# tm8_XP1.net
KiCad netlist of a schematic drawn in EAGLE
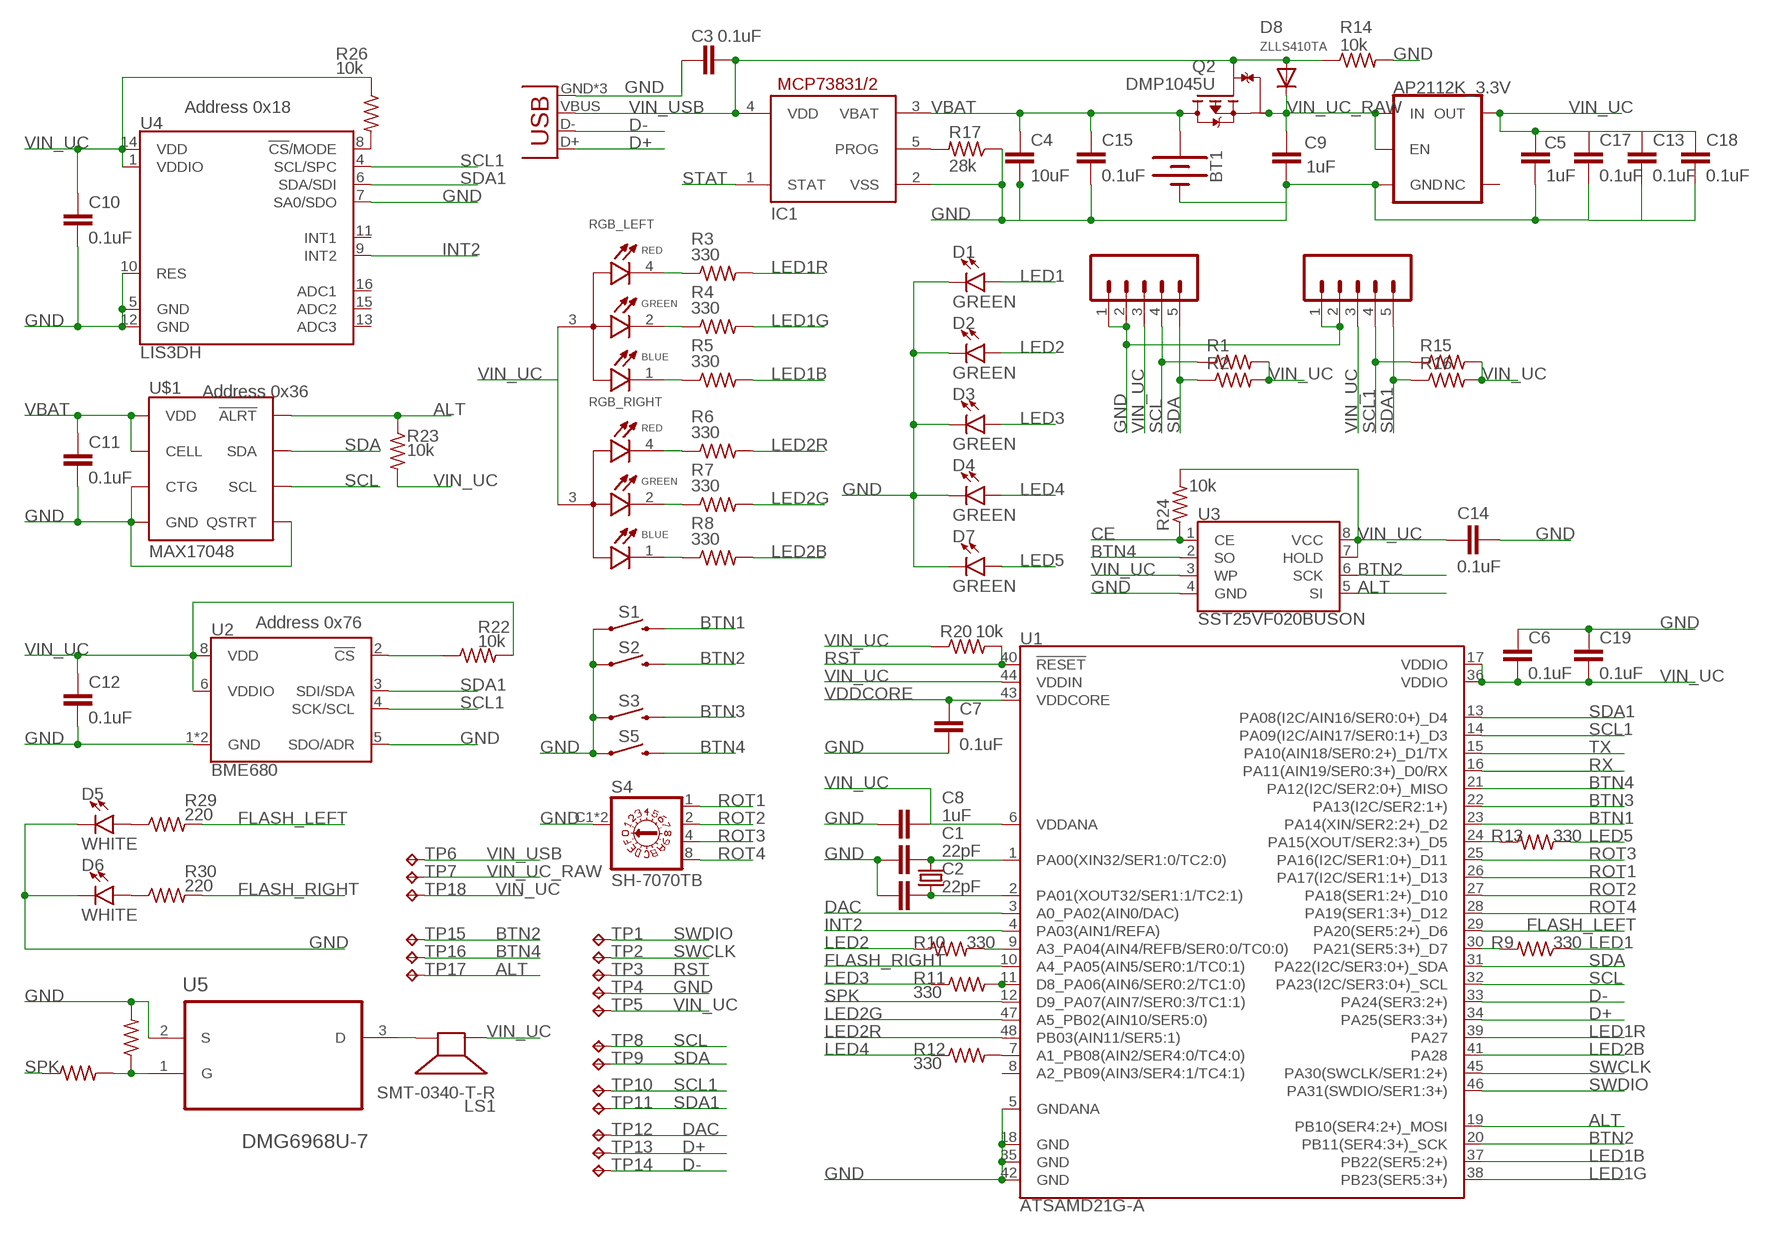
[diagram p0: schematic, sheet 1]

(export (version "E")
  (design (tool "Eeschema 10.0.6"))
  (components
    (comp (ref "AP2112K_3.3V")
      (value "3.3V")
      (footprint "eagle-import:SOT23-5")
      (libsource (lib "eagle-import") (part "V_REG_AP2112K-3.3V"))
    )
    (comp (ref "BT1")
      (value "BATTERY-20MM_SMD_4LEGS_OVERPASTE_INNER")
      (footprint "eagle-import:BATTCON_20MM_4LEGS_OVERPASTE_INNER")
      (libsource (lib "eagle-import") (part "BATTERY-20MM_SMD_4LEGS_OVERPASTE_INNER"))
    )
    (comp (ref "C1")
      (value "22pF")
      (footprint "eagle-import:C0402")
      (libsource (lib "eagle-import") (part "C-EUC0402"))
    )
    (comp (ref "C2")
      (value "22pF")
      (footprint "eagle-import:C0402")
      (libsource (lib "eagle-import") (part "C-EUC0402"))
    )
    (comp (ref "C3")
      (value "0.1uF")
      (footprint "eagle-import:C0402")
      (libsource (lib "eagle-import") (part "C-EUC0402"))
    )
    (comp (ref "C4")
      (value "10uF")
      (footprint "eagle-import:C0402")
      (libsource (lib "eagle-import") (part "C-EUC0402"))
    )
    (comp (ref "C5")
      (value "1uF")
      (footprint "eagle-import:C0402")
      (libsource (lib "eagle-import") (part "C-EUC0402"))
    )
    (comp (ref "C6")
      (value "0.1uF")
      (footprint "eagle-import:C0402")
      (libsource (lib "eagle-import") (part "C-EUC0402"))
    )
    (comp (ref "C7")
      (value "0.1uF")
      (footprint "eagle-import:C0402")
      (libsource (lib "eagle-import") (part "C-EUC0402"))
    )
    (comp (ref "C8")
      (value "1uF")
      (footprint "eagle-import:C0402")
      (libsource (lib "eagle-import") (part "C-EUC0402"))
    )
    (comp (ref "C9")
      (value "1uF")
      (footprint "eagle-import:C0402")
      (libsource (lib "eagle-import") (part "C-EUC0402"))
    )
    (comp (ref "C10")
      (value "0.1uF")
      (footprint "eagle-import:C0402")
      (libsource (lib "eagle-import") (part "C-EUC0402"))
    )
    (comp (ref "C11")
      (value "0.1uF")
      (footprint "eagle-import:C0402")
      (libsource (lib "eagle-import") (part "C-EUC0402"))
    )
    (comp (ref "C12")
      (value "0.1uF")
      (footprint "eagle-import:C0402")
      (libsource (lib "eagle-import") (part "C-EUC0402"))
    )
    (comp (ref "C13")
      (value "0.1uF")
      (footprint "eagle-import:C0402")
      (libsource (lib "eagle-import") (part "C-EUC0402"))
    )
    (comp (ref "C14")
      (value "0.1uF")
      (footprint "eagle-import:C0402")
      (libsource (lib "eagle-import") (part "C-EUC0402"))
    )
    (comp (ref "C15")
      (value "0.1uF")
      (footprint "eagle-import:C0402")
      (libsource (lib "eagle-import") (part "C-EUC0402"))
    )
    (comp (ref "C17")
      (value "0.1uF")
      (footprint "eagle-import:C0402")
      (libsource (lib "eagle-import") (part "C-EUC0402"))
    )
    (comp (ref "C18")
      (value "0.1uF")
      (footprint "eagle-import:C0402")
      (libsource (lib "eagle-import") (part "C-EUC0402"))
    )
    (comp (ref "C19")
      (value "0.1uF")
      (footprint "eagle-import:C0402")
      (libsource (lib "eagle-import") (part "C-EUC0402"))
    )
    (comp (ref "D1")
      (value "GREEN")
      (footprint "eagle-import:LED-1206")
      (libsource (lib "eagle-import") (part "LED-GREEN1206"))
    )
    (comp (ref "D2")
      (value "GREEN")
      (footprint "eagle-import:LED-1206")
      (libsource (lib "eagle-import") (part "LED-GREEN1206"))
    )
    (comp (ref "D3")
      (value "GREEN")
      (footprint "eagle-import:LED-1206")
      (libsource (lib "eagle-import") (part "LED-GREEN1206"))
    )
    (comp (ref "D4")
      (value "GREEN")
      (footprint "eagle-import:LED-1206")
      (libsource (lib "eagle-import") (part "LED-GREEN1206"))
    )
    (comp (ref "D5")
      (value "WHITE")
      (footprint "eagle-import:LED-1206")
      (libsource (lib "eagle-import") (part "LED-WHITE1206"))
    )
    (comp (ref "D6")
      (value "WHITE")
      (footprint "eagle-import:LED-1206")
      (libsource (lib "eagle-import") (part "LED-WHITE1206"))
    )
    (comp (ref "D7")
      (value "GREEN")
      (footprint "eagle-import:LED-1206")
      (libsource (lib "eagle-import") (part "LED-GREEN1206"))
    )
    (comp (ref "D8")
      (value "ZLLS410TA")
      (footprint "eagle-import:SOD-323F")
      (libsource (lib "eagle-import") (part "DIODESOD-323F"))
    )
    (comp (ref "IC1")
      (value "MCP73831/OT")
      (footprint "eagle-import:SOT23-5L")
      (libsource (lib "eagle-import") (part "MCP73831/OT"))
    )
    (comp (ref "JP2")
      (value "USB-MICROB")
      (footprint "eagle-import:USB-MICROB")
      (libsource (lib "eagle-import") (part "USB-MICROB"))
    )
    (comp (ref "LCD1")
      (value "CONN_05VERT_FEMALE_HEADER")
      (footprint "eagle-import:1X05_SMD_VERTICAL_COMBO")
      (libsource (lib "eagle-import") (part "CONN_05VERT_FEMALE_HEADER"))
    )
    (comp (ref "LCD2")
      (value "CONN_05VERT_FEMALE_HEADER")
      (footprint "eagle-import:1X05_SMD_VERTICAL_COMBO")
      (libsource (lib "eagle-import") (part "CONN_05VERT_FEMALE_HEADER"))
    )
    (comp (ref "LS1")
      (value "SMT-0340-T-R")
      (footprint "eagle-import:XDCR_SMT-0340-T-R")
      (fields (field (name "MANUFACTURER") "Pui Audio"))
      (libsource (lib "eagle-import") (part "SMT-0340-T-R"))
    )
    (comp (ref "Q2")
      (value "DMP1045U")
      (footprint "eagle-import:SOT91P240X110-3N")
      (fields (field (name "MF") "Diodes Inc."))
      (libsource (lib "eagle-import") (part "DMP1045U"))
    )
    (comp (ref "R1")
      (value "R-US_R0402")
      (footprint "eagle-import:R0402")
      (libsource (lib "eagle-import") (part "adafruit_25768682_R-US_R0402"))
    )
    (comp (ref "R2")
      (value "R-US_R0402")
      (footprint "eagle-import:R0402")
      (libsource (lib "eagle-import") (part "adafruit_25768682_R-US_R0402"))
    )
    (comp (ref "R3")
      (value "330")
      (footprint "eagle-import:R0402")
      (libsource (lib "eagle-import") (part "rcl_334_R-US_R0402"))
    )
    (comp (ref "R4")
      (value "330")
      (footprint "eagle-import:R0402")
      (libsource (lib "eagle-import") (part "rcl_334_R-US_R0402"))
    )
    (comp (ref "R5")
      (value "330")
      (footprint "eagle-import:R0402")
      (libsource (lib "eagle-import") (part "rcl_334_R-US_R0402"))
    )
    (comp (ref "R6")
      (value "330")
      (footprint "eagle-import:R0402")
      (libsource (lib "eagle-import") (part "rcl_334_R-US_R0402"))
    )
    (comp (ref "R7")
      (value "330")
      (footprint "eagle-import:R0402")
      (libsource (lib "eagle-import") (part "rcl_334_R-US_R0402"))
    )
    (comp (ref "R8")
      (value "330")
      (footprint "eagle-import:R0402")
      (libsource (lib "eagle-import") (part "rcl_334_R-US_R0402"))
    )
    (comp (ref "R9")
      (value "330")
      (footprint "eagle-import:R0402")
      (libsource (lib "eagle-import") (part "rcl_334_R-US_R0402"))
    )
    (comp (ref "R10")
      (value "330")
      (footprint "eagle-import:R0402")
      (libsource (lib "eagle-import") (part "rcl_334_R-US_R0402"))
    )
    (comp (ref "R11")
      (value "330")
      (footprint "eagle-import:R0402")
      (libsource (lib "eagle-import") (part "rcl_334_R-US_R0402"))
    )
    (comp (ref "R12")
      (value "330")
      (footprint "eagle-import:R0402")
      (libsource (lib "eagle-import") (part "rcl_334_R-US_R0402"))
    )
    (comp (ref "R13")
      (value "330")
      (footprint "eagle-import:R0402")
      (libsource (lib "eagle-import") (part "rcl_334_R-US_R0402"))
    )
    (comp (ref "R14")
      (value "10k")
      (footprint "eagle-import:R0402")
      (libsource (lib "eagle-import") (part "R-US_R0402"))
    )
    (comp (ref "R15")
      (value "R-US_R0402")
      (footprint "eagle-import:R0402")
      (libsource (lib "eagle-import") (part "adafruit_25768682_R-US_R0402"))
    )
    (comp (ref "R16")
      (value "R-US_R0402")
      (footprint "eagle-import:R0402")
      (libsource (lib "eagle-import") (part "adafruit_25768682_R-US_R0402"))
    )
    (comp (ref "R17")
      (value "28k")
      (footprint "eagle-import:R0402")
      (libsource (lib "eagle-import") (part "adafruit_25768682_R-US_R0402"))
    )
    (comp (ref "R18")
      (value "220")
      (footprint "eagle-import:R0402")
      (libsource (lib "eagle-import") (part "rcl_334_R-US_R0402"))
    )
    (comp (ref "R19")
      (value "220")
      (footprint "eagle-import:R0402")
      (libsource (lib "eagle-import") (part "rcl_334_R-US_R0402"))
    )
    (comp (ref "R20")
      (value "10k")
      (footprint "eagle-import:R0402")
      (libsource (lib "eagle-import") (part "adafruit_25768682_R-US_R0402"))
    )
    (comp (ref "R22")
      (value "10k")
      (footprint "eagle-import:R0402")
      (libsource (lib "eagle-import") (part "rcl_334_R-US_R0402"))
    )
    (comp (ref "R23")
      (value "10k")
      (footprint "eagle-import:R0402")
      (libsource (lib "eagle-import") (part "rcl_334_R-US_R0402"))
    )
    (comp (ref "R24")
      (value "10k")
      (footprint "eagle-import:R0402")
      (libsource (lib "eagle-import") (part "rcl_334_R-US_R0402"))
    )
    (comp (ref "R26")
      (value "10k")
      (footprint "eagle-import:R0402")
      (libsource (lib "eagle-import") (part "rcl_334_R-US_R0402"))
    )
    (comp (ref "R29")
      (value "220")
      (footprint "eagle-import:R0402")
      (libsource (lib "eagle-import") (part "rcl_334_R-US_R0402"))
    )
    (comp (ref "R30")
      (value "220")
      (footprint "eagle-import:R0402")
      (libsource (lib "eagle-import") (part "rcl_334_R-US_R0402"))
    )
    (comp (ref "RGB_LEFT")
      (value "EAST1616RGBA3")
      (footprint "eagle-import:LED_EAST1616RGBA3")
      (fields (field (name "MF") "Everlight Electronics"))
      (libsource (lib "eagle-import") (part "EAST1616RGBA3"))
    )
    (comp (ref "RGB_RIGHT")
      (value "EAST1616RGBA3")
      (footprint "eagle-import:LED_EAST1616RGBA3")
      (fields (field (name "MF") "Everlight Electronics"))
      (libsource (lib "eagle-import") (part "EAST1616RGBA3"))
    )
    (comp (ref "S1")
      (value "MOMENTARY-SWITCH-SPST-SMD-6.0X3.5MM")
      (footprint "eagle-import:TACTILE_SWITCH_SMD_6.0X3.5MM")
      (libsource (lib "eagle-import") (part "MOMENTARY-SWITCH-SPST-SMD-6.0X3.5MM"))
    )
    (comp (ref "S2")
      (value "MOMENTARY-SWITCH-SPST-SMD-6.0X3.5MM")
      (footprint "eagle-import:TACTILE_SWITCH_SMD_6.0X3.5MM")
      (libsource (lib "eagle-import") (part "MOMENTARY-SWITCH-SPST-SMD-6.0X3.5MM"))
    )
    (comp (ref "S3")
      (value "MOMENTARY-SWITCH-SPST-SMD-6.0X3.5MM")
      (footprint "eagle-import:TACTILE_SWITCH_SMD_6.0X3.5MM")
      (libsource (lib "eagle-import") (part "MOMENTARY-SWITCH-SPST-SMD-6.0X3.5MM"))
    )
    (comp (ref "S4")
      (value "SH-7070TB")
      (footprint "eagle-import:SH-7070B")
      (fields (field (name "MF") "Nidec Copal"))
      (libsource (lib "eagle-import") (part "SH-7070TB"))
    )
    (comp (ref "S5")
      (value "MOMENTARY-SWITCH-SPST-SMD-6.0X3.5MM")
      (footprint "eagle-import:TACTILE_SWITCH_SMD_6.0X3.5MM")
      (libsource (lib "eagle-import") (part "MOMENTARY-SWITCH-SPST-SMD-6.0X3.5MM"))
    )
    (comp (ref "TP1")
      (value "TPTP14R")
      (footprint "eagle-import:TP14R")
      (libsource (lib "eagle-import") (part "TPTP14R"))
    )
    (comp (ref "TP2")
      (value "TPTP14R")
      (footprint "eagle-import:TP14R")
      (libsource (lib "eagle-import") (part "TPTP14R"))
    )
    (comp (ref "TP3")
      (value "TPTP14R")
      (footprint "eagle-import:TP14R")
      (libsource (lib "eagle-import") (part "TPTP14R"))
    )
    (comp (ref "TP4")
      (value "TPTP14R")
      (footprint "eagle-import:TP14R")
      (libsource (lib "eagle-import") (part "TPTP14R"))
    )
    (comp (ref "TP5")
      (value "TPTP14R")
      (footprint "eagle-import:TP14R")
      (libsource (lib "eagle-import") (part "TPTP14R"))
    )
    (comp (ref "TP6")
      (value "TPTP14R")
      (footprint "eagle-import:TP14R")
      (libsource (lib "eagle-import") (part "TPTP14R"))
    )
    (comp (ref "TP7")
      (value "TPTP14R")
      (footprint "eagle-import:TP14R")
      (libsource (lib "eagle-import") (part "TPTP14R"))
    )
    (comp (ref "TP8")
      (value "TPTP14R")
      (footprint "eagle-import:TP14R")
      (libsource (lib "eagle-import") (part "TPTP14R"))
    )
    (comp (ref "TP9")
      (value "TPTP14R")
      (footprint "eagle-import:TP14R")
      (libsource (lib "eagle-import") (part "TPTP14R"))
    )
    (comp (ref "TP10")
      (value "TPTP14R")
      (footprint "eagle-import:TP14R")
      (libsource (lib "eagle-import") (part "TPTP14R"))
    )
    (comp (ref "TP11")
      (value "TPTP14R")
      (footprint "eagle-import:TP14R")
      (libsource (lib "eagle-import") (part "TPTP14R"))
    )
    (comp (ref "TP12")
      (value "TPTP14R")
      (footprint "eagle-import:TP14R")
      (libsource (lib "eagle-import") (part "TPTP14R"))
    )
    (comp (ref "TP13")
      (value "TPTP14R")
      (footprint "eagle-import:TP14R")
      (libsource (lib "eagle-import") (part "TPTP14R"))
    )
    (comp (ref "TP14")
      (value "TPTP14R")
      (footprint "eagle-import:TP14R")
      (libsource (lib "eagle-import") (part "TPTP14R"))
    )
    (comp (ref "TP15")
      (value "TPTP14R")
      (footprint "eagle-import:TP14R")
      (libsource (lib "eagle-import") (part "TPTP14R"))
    )
    (comp (ref "TP16")
      (value "TPTP14R")
      (footprint "eagle-import:TP14R")
      (libsource (lib "eagle-import") (part "TPTP14R"))
    )
    (comp (ref "TP17")
      (value "TPTP14R")
      (footprint "eagle-import:TP14R")
      (libsource (lib "eagle-import") (part "TPTP14R"))
    )
    (comp (ref "TP18")
      (value "TPTP14R")
      (footprint "eagle-import:TP14R")
      (libsource (lib "eagle-import") (part "TPTP14R"))
    )
    (comp (ref "U$1")
      (value "MAX17048")
      (footprint "eagle-import:DFN-8")
      (libsource (lib "eagle-import") (part "MAX17048DFN8"))
    )
    (comp (ref "U1")
      (value "ATSAMD21G-A")
      (footprint "eagle-import:TQFP-48")
      (libsource (lib "eagle-import") (part "ATSAMD21G-A"))
    )
    (comp (ref "U2")
      (value "BME680")
      (footprint "eagle-import:LGA3.0X3.0")
      (libsource (lib "eagle-import") (part "BME680-LGA"))
    )
    (comp (ref "U3")
      (value "SST25VF020BUSON")
      (footprint "eagle-import:USON_3X2MM")
      (fields
        (field (name "DIGIKEY_PART") "SST25VF020B-80-4I-Q3AE-TCT-ND")
        (field (name "MANU_PART") "SST25VF020B-80-4I-Q3AE-T")
      )
      (libsource (lib "eagle-import") (part "SST25VF020BUSON"))
    )
    (comp (ref "U4")
      (value "LIS3DH")
      (footprint "eagle-import:LGA-16-3X3")
      (libsource (lib "eagle-import") (part "LIS3DH"))
    )
    (comp (ref "U5")
      (value "DMG6968U-7")
      (footprint "eagle-import:SOT95P240X110-3N")
      (fields (field (name "MF") "Diodes Inc."))
      (libsource (lib "eagle-import") (part "DMG6968U-7"))
    )
    (comp (ref "Y1")
      (value "32.768kHz")
      (footprint "eagle-import:CRYSTAL-SMD-3.2X1.5MM")
      (libsource (lib "eagle-import") (part "CRYSTAL-32.768KHZSMD-3.2X1.5"))
    )
  )
  (nets
    (net (code "1") (name "/ALT") (class "Default")
      (node (ref "R23") (pin "1") (pinfunction "1_1") (pintype "passive"))
      (node (ref "TP17") (pin "TP") (pinfunction "TP_TP") (pintype "input"))
      (node (ref "U$1") (pin "P$5") (pinfunction "~{ALRT}_P$5") (pintype "bidirectional"))
      (node (ref "U1") (pin "19") (pinfunction "PB10(SER4:2+)_MOSI_19") (pintype "bidirectional"))
      (node (ref "U3") (pin "5") (pinfunction "SI_5") (pintype "bidirectional"))
    )
    (net (code "2") (name "/BTN1") (class "Default")
      (node (ref "S1") (pin "2") (pinfunction "2_2") (pintype "passive"))
      (node (ref "U1") (pin "23") (pinfunction "PA14(XIN/SER2:2+)_D2_23") (pintype "bidirectional"))
    )
    (net (code "3") (name "/BTN2") (class "Default")
      (node (ref "S2") (pin "2") (pinfunction "2_2") (pintype "passive"))
      (node (ref "TP15") (pin "TP") (pinfunction "TP_TP") (pintype "input"))
      (node (ref "U1") (pin "20") (pinfunction "PB11(SER4:3+)_SCK_20") (pintype "bidirectional"))
      (node (ref "U3") (pin "6") (pinfunction "SCK_6") (pintype "bidirectional"))
    )
    (net (code "4") (name "/BTN3") (class "Default")
      (node (ref "S3") (pin "2") (pinfunction "2_2") (pintype "passive"))
      (node (ref "U1") (pin "22") (pinfunction "PA13(I2C/SER2:1+)_22") (pintype "bidirectional"))
    )
    (net (code "5") (name "/BTN4") (class "Default")
      (node (ref "S5") (pin "2") (pinfunction "2_2") (pintype "passive"))
      (node (ref "TP16") (pin "TP") (pinfunction "TP_TP") (pintype "input"))
      (node (ref "U1") (pin "21") (pinfunction "PA12(I2C/SER2:0+)_MISO_21") (pintype "bidirectional"))
      (node (ref "U3") (pin "2") (pinfunction "SO_2") (pintype "bidirectional"))
    )
    (net (code "6") (name "/CE") (class "Default")
      (node (ref "R24") (pin "1") (pinfunction "1_1") (pintype "passive"))
      (node (ref "U3") (pin "1") (pinfunction "CE_1") (pintype "bidirectional"))
    )
    (net (code "7") (name "/D+") (class "Default")
      (node (ref "JP2") (pin "D+") (pinfunction "D+_D+") (pintype "bidirectional"))
      (node (ref "TP13") (pin "TP") (pinfunction "TP_TP") (pintype "input"))
      (node (ref "U1") (pin "34") (pinfunction "PA25(SER3:3+)_34") (pintype "bidirectional"))
    )
    (net (code "8") (name "/D-") (class "Default")
      (node (ref "JP2") (pin "D-") (pinfunction "D-_D-") (pintype "bidirectional"))
      (node (ref "TP14") (pin "TP") (pinfunction "TP_TP") (pintype "input"))
      (node (ref "U1") (pin "33") (pinfunction "PA24(SER3:2+)_33") (pintype "bidirectional"))
    )
    (net (code "9") (name "/DAC") (class "Default")
      (node (ref "TP12") (pin "TP") (pinfunction "TP_TP") (pintype "input"))
      (node (ref "U1") (pin "3") (pinfunction "A0_PA02(AIN0/DAC)_3") (pintype "bidirectional"))
    )
    (net (code "10") (name "/FLASH_LEFT") (class "Default")
      (node (ref "R29") (pin "2") (pinfunction "2_2") (pintype "passive"))
      (node (ref "U1") (pin "29") (pinfunction "PA20(SER5:2+)_D6_29") (pintype "bidirectional"))
    )
    (net (code "11") (name "/FLASH_RIGHT") (class "Default")
      (node (ref "R30") (pin "2") (pinfunction "2_2") (pintype "passive"))
      (node (ref "U1") (pin "10") (pinfunction "A4_PA05(AIN5/SER0:1/TC0:1)_10") (pintype "bidirectional"))
    )
    (net (code "12") (name "/GND") (class "Default")
      (node (ref "AP2112K_3.3V") (pin "2") (pinfunction "GND_2") (pintype "input"))
      (node (ref "BT1") (pin "2") (pinfunction "-_2") (pintype "power_in"))
      (node (ref "C1") (pin "1") (pinfunction "1_1") (pintype "passive"))
      (node (ref "C10") (pin "2") (pinfunction "2_2") (pintype "passive"))
      (node (ref "C11") (pin "2") (pinfunction "2_2") (pintype "passive"))
      (node (ref "C12") (pin "2") (pinfunction "2_2") (pintype "passive"))
      (node (ref "C13") (pin "2") (pinfunction "2_2") (pintype "passive"))
      (node (ref "C14") (pin "2") (pinfunction "2_2") (pintype "passive"))
      (node (ref "C15") (pin "2") (pinfunction "2_2") (pintype "passive"))
      (node (ref "C17") (pin "2") (pinfunction "2_2") (pintype "passive"))
      (node (ref "C18") (pin "2") (pinfunction "2_2") (pintype "passive"))
      (node (ref "C19") (pin "1") (pinfunction "1_1") (pintype "passive"))
      (node (ref "C2") (pin "1") (pinfunction "1_1") (pintype "passive"))
      (node (ref "C3") (pin "1") (pinfunction "1_1") (pintype "passive"))
      (node (ref "C4") (pin "2") (pinfunction "2_2") (pintype "passive"))
      (node (ref "C5") (pin "2") (pinfunction "2_2") (pintype "passive"))
      (node (ref "C6") (pin "1") (pinfunction "1_1") (pintype "passive"))
      (node (ref "C7") (pin "2") (pinfunction "2_2") (pintype "passive"))
      (node (ref "C8") (pin "1") (pinfunction "1_1") (pintype "passive"))
      (node (ref "C9") (pin "2") (pinfunction "2_2") (pintype "passive"))
      (node (ref "D1") (pin "C") (pinfunction "C_C") (pintype "passive"))
      (node (ref "D2") (pin "C") (pinfunction "C_C") (pintype "passive"))
      (node (ref "D3") (pin "C") (pinfunction "C_C") (pintype "passive"))
      (node (ref "D4") (pin "C") (pinfunction "C_C") (pintype "passive"))
      (node (ref "D5") (pin "C") (pinfunction "C_C") (pintype "passive"))
      (node (ref "D6") (pin "C") (pinfunction "C_C") (pintype "passive"))
      (node (ref "D7") (pin "C") (pinfunction "C_C") (pintype "passive"))
      (node (ref "IC1") (pin "2") (pinfunction "VSS_2") (pintype "power_in"))
      (node (ref "JP2") (pin "GND") (pinfunction "GND_GND") (pintype "bidirectional"))
      (node (ref "JP2") (pin "MT1") (pinfunction "GND_MT1") (pintype "bidirectional"))
      (node (ref "JP2") (pin "MT2") (pinfunction "GND_MT2") (pintype "bidirectional"))
      (node (ref "LCD1") (pin "1") (pinfunction "1_1") (pintype "passive"))
      (node (ref "LCD1") (pin "2") (pinfunction "2_2") (pintype "passive"))
      (node (ref "LCD2") (pin "1") (pinfunction "1_1") (pintype "passive"))
      (node (ref "LCD2") (pin "2") (pinfunction "2_2") (pintype "passive"))
      (node (ref "R14") (pin "2") (pinfunction "2_2") (pintype "passive"))
      (node (ref "R17") (pin "1") (pinfunction "1_1") (pintype "passive"))
      (node (ref "R19") (pin "2") (pinfunction "2_2") (pintype "passive"))
      (node (ref "S1") (pin "1") (pinfunction "1_1") (pintype "passive"))
      (node (ref "S2") (pin "1") (pinfunction "1_1") (pintype "passive"))
      (node (ref "S3") (pin "1") (pinfunction "1_1") (pintype "passive"))
      (node (ref "S4") (pin "C1") (pinfunction "C_C1") (pintype "passive"))
      (node (ref "S4") (pin "C2") (pinfunction "C_C2") (pintype "passive"))
      (node (ref "S5") (pin "1") (pinfunction "1_1") (pintype "passive"))
      (node (ref "TP4") (pin "TP") (pinfunction "TP_TP") (pintype "input"))
      (node (ref "U$1") (pin "P$1") (pinfunction "CTG_P$1") (pintype "input"))
      (node (ref "U$1") (pin "P$4") (pinfunction "GND_P$4") (pintype "bidirectional"))
      (node (ref "U$1") (pin "P$6") (pinfunction "QSTRT_P$6") (pintype "bidirectional"))
      (node (ref "U$1") (pin "P$9") (pinfunction "GND_P$9") (pintype "bidirectional"))
      (node (ref "U1") (pin "18") (pinfunction "GND_18") (pintype "bidirectional"))
      (node (ref "U1") (pin "35") (pinfunction "GND_35") (pintype "bidirectional"))
      (node (ref "U1") (pin "42") (pinfunction "GND_42") (pintype "bidirectional"))
      (node (ref "U1") (pin "5") (pinfunction "GNDANA_5") (pintype "bidirectional"))
      (node (ref "U2") (pin "1") (pinfunction "GND_1") (pintype "bidirectional"))
      (node (ref "U2") (pin "5") (pinfunction "SDO/ADR_5") (pintype "bidirectional"))
      (node (ref "U2") (pin "7") (pinfunction "GND_7") (pintype "bidirectional"))
      (node (ref "U3") (pin "4") (pinfunction "GND_4") (pintype "power_in"))
      (node (ref "U4") (pin "10") (pinfunction "RES_10") (pintype "bidirectional"))
      (node (ref "U4") (pin "12") (pinfunction "GND_12") (pintype "bidirectional"))
      (node (ref "U4") (pin "5") (pinfunction "GND_5") (pintype "bidirectional"))
      (node (ref "U4") (pin "7") (pinfunction "SA0/SDO_7") (pintype "bidirectional"))
      (node (ref "U5") (pin "2") (pinfunction "S_2") (pintype "passive"))
    )
    (net (code "13") (name "/INT2") (class "Default")
      (node (ref "U1") (pin "4") (pinfunction "PA03(AIN1/REFA)_4") (pintype "bidirectional"))
      (node (ref "U4") (pin "9") (pinfunction "INT2_9") (pintype "bidirectional"))
    )
    (net (code "14") (name "/LED1") (class "Default")
      (node (ref "D1") (pin "A") (pinfunction "A_A") (pintype "passive"))
      (node (ref "R9") (pin "1") (pinfunction "1_1") (pintype "passive"))
    )
    (net (code "15") (name "/LED1B") (class "Default")
      (node (ref "R5") (pin "2") (pinfunction "2_2") (pintype "passive"))
      (node (ref "U1") (pin "37") (pinfunction "PB22(SER5:2+)_37") (pintype "bidirectional"))
    )
    (net (code "16") (name "/LED1G") (class "Default")
      (node (ref "R4") (pin "2") (pinfunction "2_2") (pintype "passive"))
      (node (ref "U1") (pin "38") (pinfunction "PB23(SER5:3+)_38") (pintype "bidirectional"))
    )
    (net (code "17") (name "/LED1R") (class "Default")
      (node (ref "R3") (pin "2") (pinfunction "2_2") (pintype "passive"))
      (node (ref "U1") (pin "39") (pinfunction "PA27_39") (pintype "bidirectional"))
    )
    (net (code "18") (name "/LED2") (class "Default")
      (node (ref "D2") (pin "A") (pinfunction "A_A") (pintype "passive"))
      (node (ref "R10") (pin "1") (pinfunction "1_1") (pintype "passive"))
    )
    (net (code "19") (name "/LED2B") (class "Default")
      (node (ref "R8") (pin "2") (pinfunction "2_2") (pintype "passive"))
      (node (ref "U1") (pin "41") (pinfunction "PA28_41") (pintype "bidirectional"))
    )
    (net (code "20") (name "/LED2G") (class "Default")
      (node (ref "R7") (pin "2") (pinfunction "2_2") (pintype "passive"))
      (node (ref "U1") (pin "47") (pinfunction "A5_PB02(AIN10/SER5:0)_47") (pintype "bidirectional"))
    )
    (net (code "21") (name "/LED2R") (class "Default")
      (node (ref "R6") (pin "2") (pinfunction "2_2") (pintype "passive"))
      (node (ref "U1") (pin "48") (pinfunction "PB03(AIN11/SER5:1)_48") (pintype "bidirectional"))
    )
    (net (code "22") (name "/LED3") (class "Default")
      (node (ref "D3") (pin "A") (pinfunction "A_A") (pintype "passive"))
      (node (ref "R11") (pin "1") (pinfunction "1_1") (pintype "passive"))
    )
    (net (code "23") (name "/LED4") (class "Default")
      (node (ref "D4") (pin "A") (pinfunction "A_A") (pintype "passive"))
      (node (ref "R12") (pin "1") (pinfunction "1_1") (pintype "passive"))
    )
    (net (code "24") (name "/LED5") (class "Default")
      (node (ref "D7") (pin "A") (pinfunction "A_A") (pintype "passive"))
      (node (ref "R13") (pin "2") (pinfunction "2_2") (pintype "passive"))
    )
    (net (code "25") (name "/ROT1") (class "Default")
      (node (ref "S4") (pin "1") (pinfunction "1_1") (pintype "passive"))
      (node (ref "U1") (pin "26") (pinfunction "PA17(I2C/SER1:1+)_D13_26") (pintype "bidirectional"))
    )
    (net (code "26") (name "/ROT2") (class "Default")
      (node (ref "S4") (pin "2") (pinfunction "2_2") (pintype "passive"))
      (node (ref "U1") (pin "27") (pinfunction "PA18(SER1:2+)_D10_27") (pintype "bidirectional"))
    )
    (net (code "27") (name "/ROT3") (class "Default")
      (node (ref "S4") (pin "4") (pinfunction "4_4") (pintype "passive"))
      (node (ref "U1") (pin "25") (pinfunction "PA16(I2C/SER1:0+)_D11_25") (pintype "bidirectional"))
    )
    (net (code "28") (name "/ROT4") (class "Default")
      (node (ref "S4") (pin "8") (pinfunction "8_8") (pintype "passive"))
      (node (ref "U1") (pin "28") (pinfunction "PA19(SER1:3+)_D12_28") (pintype "bidirectional"))
    )
    (net (code "29") (name "/RST") (class "Default")
      (node (ref "R20") (pin "2") (pinfunction "2_2") (pintype "passive"))
      (node (ref "TP3") (pin "TP") (pinfunction "TP_TP") (pintype "input"))
      (node (ref "U1") (pin "40") (pinfunction "~{RESET}_40") (pintype "bidirectional"))
    )
    (net (code "30") (name "/RX") (class "Default")
      (node (ref "U1") (pin "16") (pinfunction "PA11(AIN19/SER0:3+)_D0/RX_16") (pintype "bidirectional"))
    )
    (net (code "31") (name "/SCL") (class "Default")
      (node (ref "LCD1") (pin "4") (pinfunction "4_4") (pintype "passive"))
      (node (ref "R1") (pin "1") (pinfunction "1_1") (pintype "passive"))
      (node (ref "TP8") (pin "TP") (pinfunction "TP_TP") (pintype "input"))
      (node (ref "U$1") (pin "P$7") (pinfunction "SCL_P$7") (pintype "output"))
      (node (ref "U1") (pin "32") (pinfunction "PA23(I2C/SER3:0+)_SCL_32") (pintype "bidirectional"))
    )
    (net (code "32") (name "/SCL1") (class "Default")
      (node (ref "LCD2") (pin "4") (pinfunction "4_4") (pintype "passive"))
      (node (ref "R15") (pin "1") (pinfunction "1_1") (pintype "passive"))
      (node (ref "TP10") (pin "TP") (pinfunction "TP_TP") (pintype "input"))
      (node (ref "U1") (pin "14") (pinfunction "PA09(I2C/AIN17/SER0:1+)_D3_14") (pintype "bidirectional"))
      (node (ref "U2") (pin "4") (pinfunction "SCK/SCL_4") (pintype "bidirectional"))
      (node (ref "U4") (pin "4") (pinfunction "SCL/SPC_4") (pintype "bidirectional"))
    )
    (net (code "33") (name "/SDA") (class "Default")
      (node (ref "LCD1") (pin "5") (pinfunction "5_5") (pintype "passive"))
      (node (ref "R2") (pin "1") (pinfunction "1_1") (pintype "passive"))
      (node (ref "TP9") (pin "TP") (pinfunction "TP_TP") (pintype "input"))
      (node (ref "U$1") (pin "P$8") (pinfunction "SDA_P$8") (pintype "input"))
      (node (ref "U1") (pin "31") (pinfunction "PA22(I2C/SER3:0+)_SDA_31") (pintype "bidirectional"))
    )
    (net (code "34") (name "/SDA1") (class "Default")
      (node (ref "LCD2") (pin "5") (pinfunction "5_5") (pintype "passive"))
      (node (ref "R16") (pin "1") (pinfunction "1_1") (pintype "passive"))
      (node (ref "TP11") (pin "TP") (pinfunction "TP_TP") (pintype "input"))
      (node (ref "U1") (pin "13") (pinfunction "PA08(I2C/AIN16/SER0:0+)_D4_13") (pintype "bidirectional"))
      (node (ref "U2") (pin "3") (pinfunction "SDI/SDA_3") (pintype "bidirectional"))
      (node (ref "U4") (pin "6") (pinfunction "SDA/SDI_6") (pintype "bidirectional"))
    )
    (net (code "35") (name "/SPK") (class "Default")
      (node (ref "R18") (pin "1") (pinfunction "1_1") (pintype "passive"))
      (node (ref "U1") (pin "12") (pinfunction "D9_PA07(AIN7/SER0:3/TC1:1)_12") (pintype "bidirectional"))
    )
    (net (code "36") (name "/STAT") (class "Default")
      (node (ref "IC1") (pin "1") (pinfunction "STAT_1") (pintype "output"))
    )
    (net (code "37") (name "/SWCLK") (class "Default")
      (node (ref "TP2") (pin "TP") (pinfunction "TP_TP") (pintype "input"))
      (node (ref "U1") (pin "45") (pinfunction "PA30(SWCLK/SER1:2+)_45") (pintype "bidirectional"))
    )
    (net (code "38") (name "/SWDIO") (class "Default")
      (node (ref "TP1") (pin "TP") (pinfunction "TP_TP") (pintype "input"))
      (node (ref "U1") (pin "46") (pinfunction "PA31(SWDIO/SER1:3+)_46") (pintype "bidirectional"))
    )
    (net (code "39") (name "/TX") (class "Default")
      (node (ref "U1") (pin "15") (pinfunction "PA10(AIN18/SER0:2+)_D1/TX_15") (pintype "bidirectional"))
    )
    (net (code "40") (name "/VBAT") (class "Default")
      (node (ref "BT1") (pin "1") (pinfunction "+_1") (pintype "power_in"))
      (node (ref "C11") (pin "1") (pinfunction "1_1") (pintype "passive"))
      (node (ref "C15") (pin "1") (pinfunction "1_1") (pintype "passive"))
      (node (ref "C4") (pin "1") (pinfunction "1_1") (pintype "passive"))
      (node (ref "IC1") (pin "3") (pinfunction "VBAT_3") (pintype "bidirectional"))
      (node (ref "Q2") (pin "3") (pinfunction "D_3") (pintype "passive"))
      (node (ref "U$1") (pin "P$2") (pinfunction "CELL_P$2") (pintype "input"))
      (node (ref "U$1") (pin "P$3") (pinfunction "VDD_P$3") (pintype "bidirectional"))
    )
    (net (code "41") (name "/VDDCORE") (class "Default")
      (node (ref "C7") (pin "1") (pinfunction "1_1") (pintype "passive"))
      (node (ref "U1") (pin "43") (pinfunction "VDDCORE_43") (pintype "bidirectional"))
    )
    (net (code "42") (name "/VIN_UC") (class "Default")
      (node (ref "AP2112K_3.3V") (pin "5") (pinfunction "OUT_5") (pintype "passive"))
      (node (ref "C10") (pin "1") (pinfunction "1_1") (pintype "passive"))
      (node (ref "C12") (pin "1") (pinfunction "1_1") (pintype "passive"))
      (node (ref "C13") (pin "1") (pinfunction "1_1") (pintype "passive"))
      (node (ref "C14") (pin "1") (pinfunction "1_1") (pintype "passive"))
      (node (ref "C17") (pin "1") (pinfunction "1_1") (pintype "passive"))
      (node (ref "C18") (pin "1") (pinfunction "1_1") (pintype "passive"))
      (node (ref "C19") (pin "2") (pinfunction "2_2") (pintype "passive"))
      (node (ref "C5") (pin "1") (pinfunction "1_1") (pintype "passive"))
      (node (ref "C6") (pin "2") (pinfunction "2_2") (pintype "passive"))
      (node (ref "C8") (pin "2") (pinfunction "2_2") (pintype "passive"))
      (node (ref "LCD1") (pin "3") (pinfunction "3_3") (pintype "passive"))
      (node (ref "LCD2") (pin "3") (pinfunction "3_3") (pintype "passive"))
      (node (ref "LS1") (pin "P") (pinfunction "P_P") (pintype "passive"))
      (node (ref "R1") (pin "2") (pinfunction "2_2") (pintype "passive"))
      (node (ref "R15") (pin "2") (pinfunction "2_2") (pintype "passive"))
      (node (ref "R16") (pin "2") (pinfunction "2_2") (pintype "passive"))
      (node (ref "R2") (pin "2") (pinfunction "2_2") (pintype "passive"))
      (node (ref "R20") (pin "1") (pinfunction "1_1") (pintype "passive"))
      (node (ref "R22") (pin "2") (pinfunction "2_2") (pintype "passive"))
      (node (ref "R23") (pin "2") (pinfunction "2_2") (pintype "passive"))
      (node (ref "R24") (pin "2") (pinfunction "2_2") (pintype "passive"))
      (node (ref "R26") (pin "1") (pinfunction "1_1") (pintype "passive"))
      (node (ref "RGB_LEFT") (pin "3") (pinfunction "A_3") (pintype "passive"))
      (node (ref "RGB_RIGHT") (pin "3") (pinfunction "A_3") (pintype "passive"))
      (node (ref "TP18") (pin "TP") (pinfunction "TP_TP") (pintype "input"))
      (node (ref "TP5") (pin "TP") (pinfunction "TP_TP") (pintype "input"))
      (node (ref "U1") (pin "17") (pinfunction "VDDIO_17") (pintype "bidirectional"))
      (node (ref "U1") (pin "36") (pinfunction "VDDIO_36") (pintype "bidirectional"))
      (node (ref "U1") (pin "44") (pinfunction "VDDIN_44") (pintype "bidirectional"))
      (node (ref "U1") (pin "6") (pinfunction "VDDANA_6") (pintype "bidirectional"))
      (node (ref "U2") (pin "6") (pinfunction "VDDIO_6") (pintype "bidirectional"))
      (node (ref "U2") (pin "8") (pinfunction "VDD_8") (pintype "bidirectional"))
      (node (ref "U3") (pin "3") (pinfunction "WP_3") (pintype "bidirectional"))
      (node (ref "U3") (pin "7") (pinfunction "HOLD_7") (pintype "bidirectional"))
      (node (ref "U3") (pin "8") (pinfunction "VCC_8") (pintype "power_in"))
      (node (ref "U4") (pin "1") (pinfunction "VDDIO_1") (pintype "bidirectional"))
      (node (ref "U4") (pin "14") (pinfunction "VDD_14") (pintype "bidirectional"))
    )
    (net (code "43") (name "/VIN_UC_RAW") (class "Default")
      (node (ref "AP2112K_3.3V") (pin "1") (pinfunction "IN_1") (pintype "input"))
      (node (ref "AP2112K_3.3V") (pin "3") (pinfunction "EN_3") (pintype "input"))
      (node (ref "C9") (pin "1") (pinfunction "1_1") (pintype "passive"))
      (node (ref "D8") (pin "C") (pinfunction "C_C") (pintype "passive"))
      (node (ref "Q2") (pin "2") (pinfunction "S_2") (pintype "passive"))
      (node (ref "TP7") (pin "TP") (pinfunction "TP_TP") (pintype "input"))
    )
    (net (code "44") (name "/VIN_USB") (class "Default")
      (node (ref "C3") (pin "2") (pinfunction "2_2") (pintype "passive"))
      (node (ref "D8") (pin "A") (pinfunction "A_A") (pintype "passive"))
      (node (ref "IC1") (pin "4") (pinfunction "VDD_4") (pintype "power_in"))
      (node (ref "JP2") (pin "VBUS") (pinfunction "VBUS_VBUS") (pintype "bidirectional"))
      (node (ref "Q2") (pin "1") (pinfunction "G_1") (pintype "passive"))
      (node (ref "R14") (pin "1") (pinfunction "1_1") (pintype "passive"))
      (node (ref "TP6") (pin "TP") (pinfunction "TP_TP") (pintype "input"))
    )
    (net (code "45") (name "Net-(D5-PadA)") (class "Default")
      (node (ref "D5") (pin "A") (pinfunction "A_A") (pintype "passive"))
      (node (ref "R29") (pin "1") (pinfunction "1_1") (pintype "passive"))
    )
    (net (code "46") (name "Net-(D6-PadA)") (class "Default")
      (node (ref "D6") (pin "A") (pinfunction "A_A") (pintype "passive"))
      (node (ref "R30") (pin "1") (pinfunction "1_1") (pintype "passive"))
    )
    (net (code "47") (name "Net-(IC1-PROG)") (class "Default")
      (node (ref "IC1") (pin "5") (pinfunction "PROG_5") (pintype "input"))
      (node (ref "R17") (pin "2") (pinfunction "2_2") (pintype "passive"))
    )
    (net (code "48") (name "Net-(RGB_LEFT-B_C)") (class "Default")
      (node (ref "R5") (pin "1") (pinfunction "1_1") (pintype "passive"))
      (node (ref "RGB_LEFT") (pin "1") (pinfunction "B_C_1") (pintype "passive"))
    )
    (net (code "49") (name "Net-(RGB_LEFT-G_C)") (class "Default")
      (node (ref "R4") (pin "1") (pinfunction "1_1") (pintype "passive"))
      (node (ref "RGB_LEFT") (pin "2") (pinfunction "G_C_2") (pintype "passive"))
    )
    (net (code "50") (name "Net-(RGB_LEFT-R_C)") (class "Default")
      (node (ref "R3") (pin "1") (pinfunction "1_1") (pintype "passive"))
      (node (ref "RGB_LEFT") (pin "4") (pinfunction "R_C_4") (pintype "passive"))
    )
    (net (code "51") (name "Net-(RGB_RIGHT-B_C)") (class "Default")
      (node (ref "R8") (pin "1") (pinfunction "1_1") (pintype "passive"))
      (node (ref "RGB_RIGHT") (pin "1") (pinfunction "B_C_1") (pintype "passive"))
    )
    (net (code "52") (name "Net-(RGB_RIGHT-G_C)") (class "Default")
      (node (ref "R7") (pin "1") (pinfunction "1_1") (pintype "passive"))
      (node (ref "RGB_RIGHT") (pin "2") (pinfunction "G_C_2") (pintype "passive"))
    )
    (net (code "53") (name "Net-(RGB_RIGHT-R_C)") (class "Default")
      (node (ref "R6") (pin "1") (pinfunction "1_1") (pintype "passive"))
      (node (ref "RGB_RIGHT") (pin "4") (pinfunction "R_C_4") (pintype "passive"))
    )
    (net (code "54") (name "Net-(U1-A1_PB08(AIN2{slash}SER4:0{slash}TC4:0))") (class "Default")
      (node (ref "R12") (pin "2") (pinfunction "2_2") (pintype "passive"))
      (node (ref "U1") (pin "7") (pinfunction "A1_PB08(AIN2/SER4:0/TC4:0)_7") (pintype "bidirectional"))
    )
    (net (code "55") (name "Net-(U1-A3_PA04(AIN4{slash}REFB{slash}SER0:0{slash}TC0:0))") (class "Default")
      (node (ref "R10") (pin "2") (pinfunction "2_2") (pintype "passive"))
      (node (ref "U1") (pin "9") (pinfunction "A3_PA04(AIN4/REFB/SER0:0/TC0:0)_9") (pintype "bidirectional"))
    )
    (net (code "56") (name "Net-(U1-D8_PA06(AIN6{slash}SER0:2{slash}TC1:0))") (class "Default")
      (node (ref "R11") (pin "2") (pinfunction "2_2") (pintype "passive"))
      (node (ref "U1") (pin "11") (pinfunction "D8_PA06(AIN6/SER0:2/TC1:0)_11") (pintype "bidirectional"))
    )
    (net (code "57") (name "Net-(U1-PA00(XIN32{slash}SER1:0{slash}TC2:0))") (class "Default")
      (node (ref "C1") (pin "2") (pinfunction "2_2") (pintype "passive"))
      (node (ref "U1") (pin "1") (pinfunction "PA00(XIN32/SER1:0/TC2:0)_1") (pintype "bidirectional"))
      (node (ref "Y1") (pin "P$2") (pinfunction "2_P$2") (pintype "passive"))
    )
    (net (code "58") (name "Net-(U1-PA01(XOUT32{slash}SER1:1{slash}TC2:1))") (class "Default")
      (node (ref "C2") (pin "2") (pinfunction "2_2") (pintype "passive"))
      (node (ref "U1") (pin "2") (pinfunction "PA01(XOUT32/SER1:1/TC2:1)_2") (pintype "bidirectional"))
      (node (ref "Y1") (pin "P$1") (pinfunction "1_P$1") (pintype "passive"))
    )
    (net (code "59") (name "Net-(U1-PA15(XOUT{slash}SER2:3+)_D5)") (class "Default")
      (node (ref "R13") (pin "1") (pinfunction "1_1") (pintype "passive"))
      (node (ref "U1") (pin "24") (pinfunction "PA15(XOUT/SER2:3+)_D5_24") (pintype "bidirectional"))
    )
    (net (code "60") (name "Net-(U1-PA21(SER5:3+)_D7)") (class "Default")
      (node (ref "R9") (pin "2") (pinfunction "2_2") (pintype "passive"))
      (node (ref "U1") (pin "30") (pinfunction "PA21(SER5:3+)_D7_30") (pintype "bidirectional"))
    )
    (net (code "61") (name "Net-(U2-~{CS})") (class "Default")
      (node (ref "R22") (pin "1") (pinfunction "1_1") (pintype "passive"))
      (node (ref "U2") (pin "2") (pinfunction "~{CS}_2") (pintype "bidirectional"))
    )
    (net (code "62") (name "Net-(U4-~{CS}{slash}MODE)") (class "Default")
      (node (ref "R26") (pin "2") (pinfunction "2_2") (pintype "passive"))
      (node (ref "U4") (pin "8") (pinfunction "~{CS}/MODE_8") (pintype "bidirectional"))
    )
    (net (code "63") (name "Net-(U5-D)") (class "Default")
      (node (ref "LS1") (pin "N") (pinfunction "N_N") (pintype "passive"))
      (node (ref "U5") (pin "3") (pinfunction "D_3") (pintype "output"))
    )
    (net (code "64") (name "Net-(U5-G)") (class "Default")
      (node (ref "R18") (pin "2") (pinfunction "2_2") (pintype "passive"))
      (node (ref "R19") (pin "1") (pinfunction "1_1") (pintype "passive"))
      (node (ref "U5") (pin "1") (pinfunction "G_1") (pintype "power_in"))
    )
    (net (code "65") (name "unconnected-(AP2112K_3.3V-NC-Pad4)") (class "Default")
      (node (ref "AP2112K_3.3V") (pin "4") (pinfunction "NC_4") (pintype "no_connect"))
    )
    (net (code "66") (name "unconnected-(U1-A2_PB09(AIN3{slash}SER4:1{slash}TC4:1)-Pad8)") (class "Default")
      (node (ref "U1") (pin "8") (pinfunction "A2_PB09(AIN3/SER4:1/TC4:1)_8") (pintype "bidirectional"))
    )
    (net (code "67") (name "unconnected-(U4-ADC1-Pad16)") (class "Default")
      (node (ref "U4") (pin "16") (pinfunction "ADC1_16") (pintype "bidirectional"))
    )
    (net (code "68") (name "unconnected-(U4-ADC2-Pad15)") (class "Default")
      (node (ref "U4") (pin "15") (pinfunction "ADC2_15") (pintype "bidirectional"))
    )
    (net (code "69") (name "unconnected-(U4-ADC3-Pad13)") (class "Default")
      (node (ref "U4") (pin "13") (pinfunction "ADC3_13") (pintype "bidirectional"))
    )
    (net (code "70") (name "unconnected-(U4-INT1-Pad11)") (class "Default")
      (node (ref "U4") (pin "11") (pinfunction "INT1_11") (pintype "bidirectional"))
    )
  )
)
